# climbing_WS2812.net
KiCad netlist of a schematic drawn in EAGLE
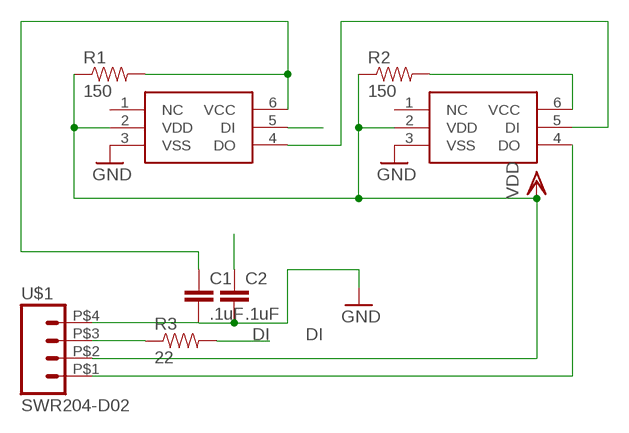
[diagram p0: schematic, sheet 1]

(export (version "E")
  (design (tool "Eeschema 10.0.6"))
  (components
    (comp (ref "C1")
      (value ".1uF")
      (footprint "eagle-import:0603-CAP")
      (libsource (lib "eagle-import") (part "CAP0603-CAP"))
    )
    (comp (ref "C2")
      (value ".1uF")
      (footprint "eagle-import:0603-CAP")
      (libsource (lib "eagle-import") (part "CAP0603-CAP"))
    )
    (comp (ref "R1")
      (value "150")
      (footprint "eagle-import:0603-RES")
      (libsource (lib "eagle-import") (part "RESISTOR0603-RES"))
    )
    (comp (ref "R2")
      (value "150")
      (footprint "eagle-import:0603-RES")
      (libsource (lib "eagle-import") (part "RESISTOR0603-RES"))
    )
    (comp (ref "R3")
      (value "22")
      (footprint "eagle-import:0603-RES")
      (libsource (lib "eagle-import") (part "RESISTOR0603-RES"))
    )
    (comp (ref "U$1")
      (value "SWR204-D02")
      (footprint "eagle-import:SWR204")
      (libsource (lib "eagle-import") (part "SWR204-D02"))
    )
    (comp (ref "U$2")
      (value "WS2812")
      (footprint "eagle-import:RGBLED5050")
      (libsource (lib "eagle-import") (part "WS2812"))
    )
    (comp (ref "U$3")
      (value "WS2812")
      (footprint "eagle-import:RGBLED5050")
      (libsource (lib "eagle-import") (part "WS2812"))
    )
  )
  (nets
    (net (code "1") (name "/DI") (class "Default")
      (node (ref "R3") (pin "2") (pinfunction "2_2") (pintype "passive"))
      (node (ref "U$2") (pin "5") (pinfunction "DI_5") (pintype "bidirectional"))
    )
    (net (code "2") (name "/VCC2") (class "Default")
      (node (ref "C2") (pin "1") (pinfunction "1_1") (pintype "passive"))
      (node (ref "R2") (pin "2") (pinfunction "2_2") (pintype "passive"))
      (node (ref "U$3") (pin "6") (pinfunction "VCC_6") (pintype "bidirectional"))
    )
    (net (code "3") (name "GND") (class "Default")
      (node (ref "C1") (pin "2") (pinfunction "2_2") (pintype "passive"))
      (node (ref "C2") (pin "2") (pinfunction "2_2") (pintype "passive"))
      (node (ref "U$1") (pin "P$4") (pinfunction "4_P$4") (pintype "passive"))
      (node (ref "U$2") (pin "3") (pinfunction "VSS_3") (pintype "bidirectional"))
      (node (ref "U$3") (pin "3") (pinfunction "VSS_3") (pintype "bidirectional"))
    )
    (net (code "4") (name "Net-(U$1-1)") (class "Default")
      (node (ref "U$1") (pin "P$1") (pinfunction "1_P$1") (pintype "passive"))
      (node (ref "U$3") (pin "4") (pinfunction "DO_4") (pintype "bidirectional"))
    )
    (net (code "5") (name "Net-(U$1-3)") (class "Default")
      (node (ref "R3") (pin "1") (pinfunction "1_1") (pintype "passive"))
      (node (ref "U$1") (pin "P$3") (pinfunction "3_P$3") (pintype "passive"))
    )
    (net (code "6") (name "Net-(U$2-DO)") (class "Default")
      (node (ref "U$2") (pin "4") (pinfunction "DO_4") (pintype "bidirectional"))
      (node (ref "U$3") (pin "5") (pinfunction "DI_5") (pintype "bidirectional"))
    )
    (net (code "7") (name "Net-(U$2-VCC)") (class "Default")
      (node (ref "C1") (pin "1") (pinfunction "1_1") (pintype "passive"))
      (node (ref "R1") (pin "2") (pinfunction "2_2") (pintype "passive"))
      (node (ref "U$2") (pin "6") (pinfunction "VCC_6") (pintype "bidirectional"))
    )
    (net (code "8") (name "VDD") (class "Default")
      (node (ref "R1") (pin "1") (pinfunction "1_1") (pintype "passive"))
      (node (ref "R2") (pin "1") (pinfunction "1_1") (pintype "passive"))
      (node (ref "U$1") (pin "P$2") (pinfunction "2_P$2") (pintype "passive"))
      (node (ref "U$2") (pin "2") (pinfunction "VDD_2") (pintype "bidirectional"))
      (node (ref "U$3") (pin "2") (pinfunction "VDD_2") (pintype "bidirectional"))
    )
    (net (code "9") (name "unconnected-(U$2-NC-Pad1)") (class "Default")
      (node (ref "U$2") (pin "1") (pinfunction "NC_1") (pintype "bidirectional"))
    )
    (net (code "10") (name "unconnected-(U$3-NC-Pad1)") (class "Default")
      (node (ref "U$3") (pin "1") (pinfunction "NC_1") (pintype "bidirectional"))
    )
  )
)
